# Electromagnet.net
KiCad netlist of a schematic drawn in EAGLE
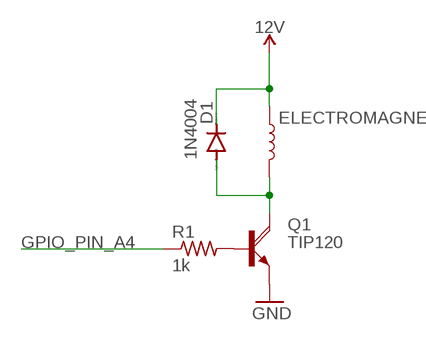
[diagram p0: schematic, sheet 1]

(export (version "E")
  (design (tool "Eeschema 10.0.6"))
  (components
    (comp (ref "D1")
      (value "1N4004")
      (footprint "eagle-import:DO41-10")
      (libsource (lib "eagle-import") (part "1N4004"))
    )
    (comp (ref "ELECTROMAGNET")
      (value "1.0μH")
      (footprint "eagle-import:0805-WIDE")
      (libsource (lib "eagle-import") (part "1.0μH-0805_WIDE-1.0μH-1.4A-0.07OHM"))
    )
    (comp (ref "Q1")
      (value "TIP120")
      (footprint "eagle-import:TO220AH")
      (libsource (lib "eagle-import") (part "TIP120"))
    )
    (comp (ref "R1")
      (value "1k")
      (footprint "eagle-import:0204V")
      (libsource (lib "eagle-import") (part "R-US_0204/2V"))
    )
  )
  (nets
    (net (code "1") (name "/GPIO_PIN_A4") (class "Default")
      (node (ref "R1") (pin "1") (pinfunction "1_1") (pintype "passive"))
    )
    (net (code "2") (name "12V") (class "Default")
      (node (ref "D1") (pin "C") (pinfunction "C_C") (pintype "passive"))
      (node (ref "ELECTROMAGNET") (pin "1") (pinfunction "1_1") (pintype "passive"))
    )
    (net (code "3") (name "GND") (class "Default")
      (node (ref "Q1") (pin "E") (pinfunction "E_E") (pintype "passive"))
    )
    (net (code "4") (name "Net-(D1-PadA)") (class "Default")
      (node (ref "D1") (pin "A") (pinfunction "A_A") (pintype "passive"))
      (node (ref "ELECTROMAGNET") (pin "2") (pinfunction "2_2") (pintype "passive"))
      (node (ref "Q1") (pin "C") (pinfunction "C_C") (pintype "passive"))
    )
    (net (code "5") (name "Net-(Q1-PadB)") (class "Default")
      (node (ref "Q1") (pin "B") (pinfunction "B_B") (pintype "passive"))
      (node (ref "R1") (pin "2") (pinfunction "2_2") (pintype "passive"))
    )
  )
)
